# VCA.net
KiCad netlist of a schematic drawn in EAGLE
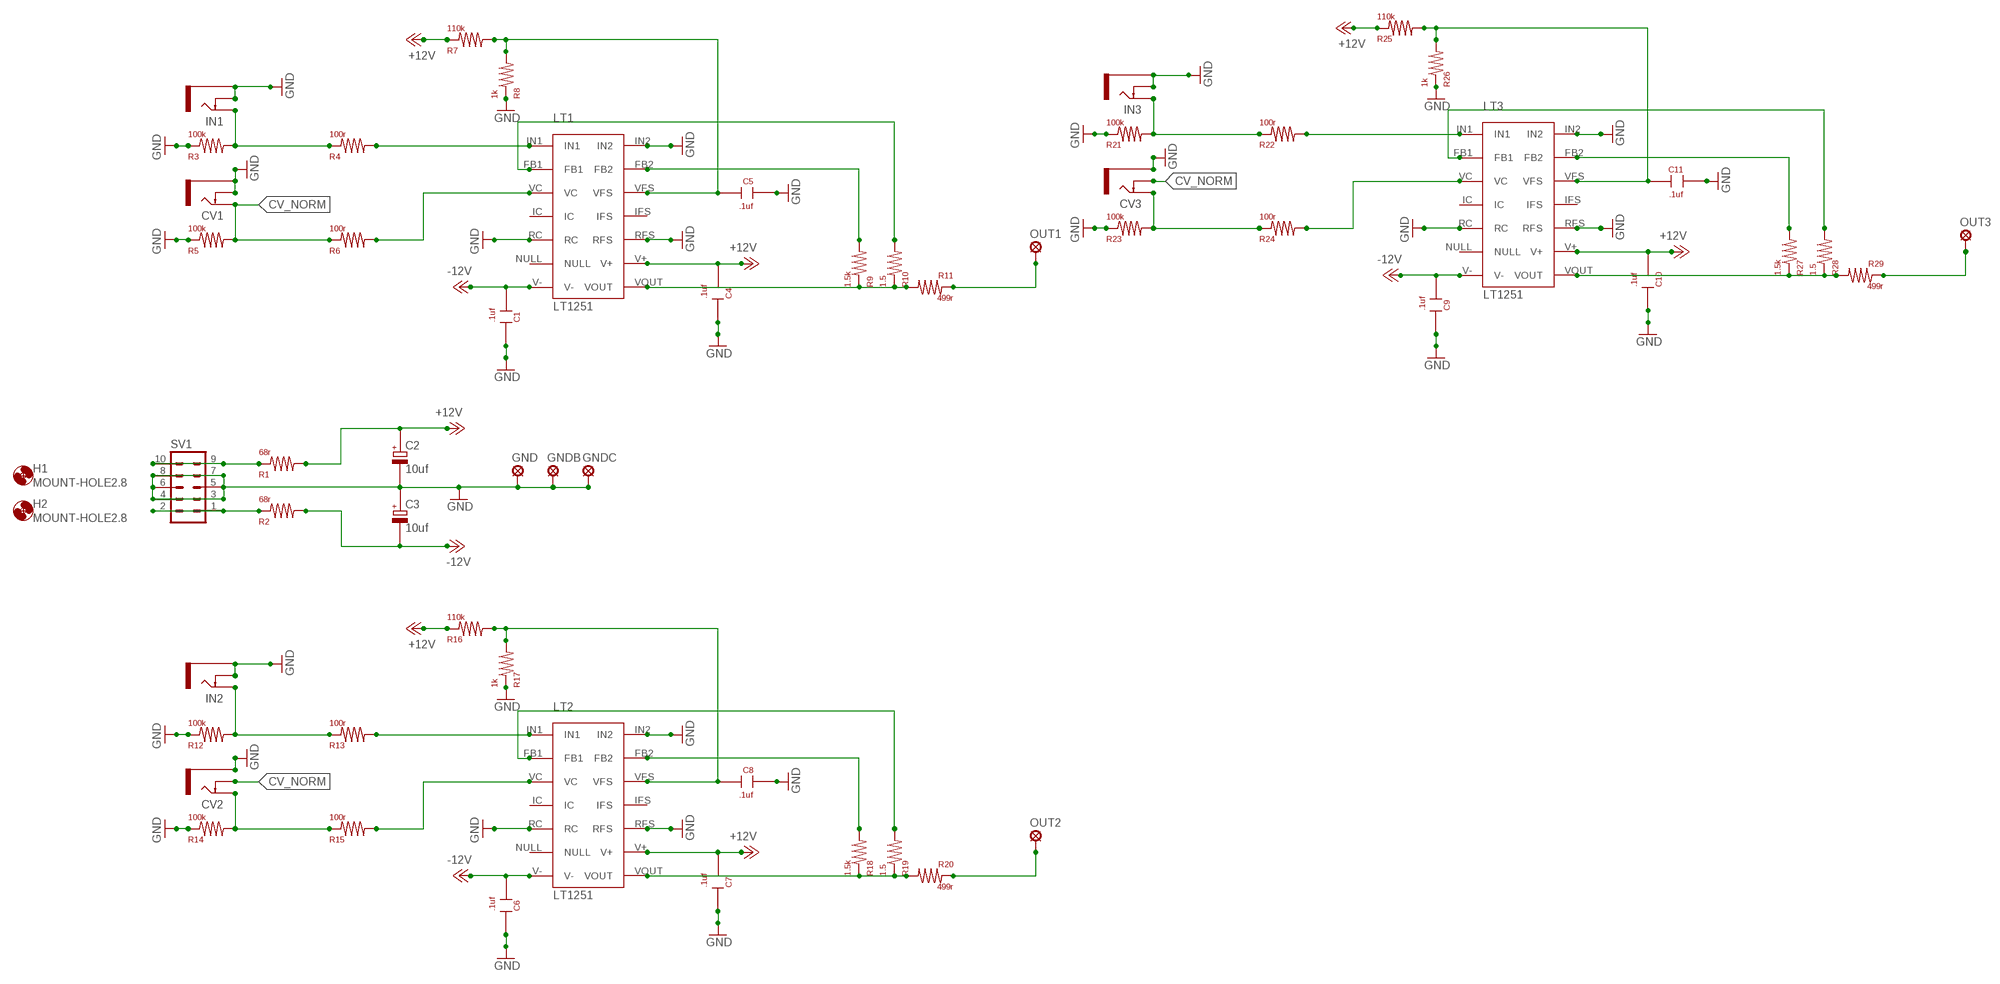
[diagram p0: schematic, sheet 1]

(export (version "E")
  (design (tool "Eeschema 10.0.6"))
  (components
    (comp (ref "C1")
      (value ".1uf")
      (footprint "eagle-import:CAPACITOR_FILM")
      (libsource (lib "eagle-import") (part "CAPACITOR_FILM"))
    )
    (comp (ref "C2")
      (value "10uf")
      (footprint "eagle-import:CAPACITOR_ELECTRO")
      (libsource (lib "eagle-import") (part "CAPACITOR_ELECTRO"))
    )
    (comp (ref "C3")
      (value "10uf")
      (footprint "eagle-import:CAPACITOR_ELECTRO")
      (libsource (lib "eagle-import") (part "CAPACITOR_ELECTRO"))
    )
    (comp (ref "C4")
      (value ".1uf")
      (footprint "eagle-import:CAPACITOR_FILM")
      (libsource (lib "eagle-import") (part "CAPACITOR_FILM"))
    )
    (comp (ref "C5")
      (value ".1uf")
      (footprint "eagle-import:CAPACITOR_FILM")
      (libsource (lib "eagle-import") (part "CAPACITOR_FILM"))
    )
    (comp (ref "C6")
      (value ".1uf")
      (footprint "eagle-import:CAPACITOR_FILM")
      (libsource (lib "eagle-import") (part "CAPACITOR_FILM"))
    )
    (comp (ref "C7")
      (value ".1uf")
      (footprint "eagle-import:CAPACITOR_FILM")
      (libsource (lib "eagle-import") (part "CAPACITOR_FILM"))
    )
    (comp (ref "C8")
      (value ".1uf")
      (footprint "eagle-import:CAPACITOR_FILM")
      (libsource (lib "eagle-import") (part "CAPACITOR_FILM"))
    )
    (comp (ref "C9")
      (value ".1uf")
      (footprint "eagle-import:CAPACITOR_FILM")
      (libsource (lib "eagle-import") (part "CAPACITOR_FILM"))
    )
    (comp (ref "C10")
      (value ".1uf")
      (footprint "eagle-import:CAPACITOR_FILM")
      (libsource (lib "eagle-import") (part "CAPACITOR_FILM"))
    )
    (comp (ref "C11")
      (value ".1uf")
      (footprint "eagle-import:CAPACITOR_FILM")
      (libsource (lib "eagle-import") (part "CAPACITOR_FILM"))
    )
    (comp (ref "CV1")
      (value "PJ302M")
      (footprint "eagle-import:PJ302M")
      (libsource (lib "eagle-import") (part "PJ302M"))
    )
    (comp (ref "CV2")
      (value "PJ302M")
      (footprint "eagle-import:PJ302M")
      (libsource (lib "eagle-import") (part "PJ302M"))
    )
    (comp (ref "CV3")
      (value "PJ302M")
      (footprint "eagle-import:PJ302M")
      (libsource (lib "eagle-import") (part "PJ302M"))
    )
    (comp (ref "GND")
      (value "LSP10")
      (footprint "eagle-import:LSP10")
      (libsource (lib "eagle-import") (part "LSP10"))
    )
    (comp (ref "GNDB")
      (value "LSP10")
      (footprint "eagle-import:LSP10")
      (libsource (lib "eagle-import") (part "LSP10"))
    )
    (comp (ref "GNDC")
      (value "LSP10")
      (footprint "eagle-import:LSP10")
      (libsource (lib "eagle-import") (part "LSP10"))
    )
    (comp (ref "H1")
      (value "MOUNT-HOLE2.8")
      (footprint "eagle-import:2,8")
      (libsource (lib "eagle-import") (part "MOUNT-HOLE2.8"))
    )
    (comp (ref "H2")
      (value "MOUNT-HOLE2.8")
      (footprint "eagle-import:2,8")
      (libsource (lib "eagle-import") (part "MOUNT-HOLE2.8"))
    )
    (comp (ref "IN1")
      (value "PJ302M")
      (footprint "eagle-import:PJ302M")
      (libsource (lib "eagle-import") (part "PJ302M"))
    )
    (comp (ref "IN2")
      (value "PJ302M")
      (footprint "eagle-import:PJ302M")
      (libsource (lib "eagle-import") (part "PJ302M"))
    )
    (comp (ref "IN3")
      (value "PJ302M")
      (footprint "eagle-import:PJ302M")
      (libsource (lib "eagle-import") (part "PJ302M"))
    )
    (comp (ref "LT1")
      (value "LT1251")
      (footprint "eagle-import:TL1251")
      (libsource (lib "eagle-import") (part "LT1251"))
    )
    (comp (ref "LT2")
      (value "LT1251")
      (footprint "eagle-import:TL1251")
      (libsource (lib "eagle-import") (part "LT1251"))
    )
    (comp (ref "LT3")
      (value "LT1251")
      (footprint "eagle-import:TL1251")
      (libsource (lib "eagle-import") (part "LT1251"))
    )
    (comp (ref "OUT1")
      (value "LSP10")
      (footprint "eagle-import:LSP10")
      (libsource (lib "eagle-import") (part "LSP10"))
    )
    (comp (ref "OUT2")
      (value "LSP10")
      (footprint "eagle-import:LSP10")
      (libsource (lib "eagle-import") (part "LSP10"))
    )
    (comp (ref "OUT3")
      (value "LSP10")
      (footprint "eagle-import:LSP10")
      (libsource (lib "eagle-import") (part "LSP10"))
    )
    (comp (ref "R1")
      (value "68r")
      (footprint "eagle-import:RESISTOR")
      (libsource (lib "eagle-import") (part "RESISTOR"))
    )
    (comp (ref "R2")
      (value "68r")
      (footprint "eagle-import:RESISTOR")
      (libsource (lib "eagle-import") (part "RESISTOR"))
    )
    (comp (ref "R3")
      (value "100k")
      (footprint "eagle-import:RESISTOR")
      (libsource (lib "eagle-import") (part "RESISTOR"))
    )
    (comp (ref "R4")
      (value "100r")
      (footprint "eagle-import:RESISTOR")
      (libsource (lib "eagle-import") (part "RESISTOR"))
    )
    (comp (ref "R5")
      (value "100k")
      (footprint "eagle-import:RESISTOR")
      (libsource (lib "eagle-import") (part "RESISTOR"))
    )
    (comp (ref "R6")
      (value "100r")
      (footprint "eagle-import:RESISTOR")
      (libsource (lib "eagle-import") (part "RESISTOR"))
    )
    (comp (ref "R7")
      (value "110k")
      (footprint "eagle-import:RESISTOR")
      (libsource (lib "eagle-import") (part "RESISTOR"))
    )
    (comp (ref "R8")
      (value "1k")
      (footprint "eagle-import:RESISTOR")
      (libsource (lib "eagle-import") (part "RESISTOR"))
    )
    (comp (ref "R9")
      (value "1.5k")
      (footprint "eagle-import:RESISTOR")
      (libsource (lib "eagle-import") (part "RESISTOR"))
    )
    (comp (ref "R10")
      (value "1.5")
      (footprint "eagle-import:RESISTOR")
      (libsource (lib "eagle-import") (part "RESISTOR"))
    )
    (comp (ref "R11")
      (value "499r")
      (footprint "eagle-import:RESISTOR")
      (libsource (lib "eagle-import") (part "RESISTOR"))
    )
    (comp (ref "R12")
      (value "100k")
      (footprint "eagle-import:RESISTOR")
      (libsource (lib "eagle-import") (part "RESISTOR"))
    )
    (comp (ref "R13")
      (value "100r")
      (footprint "eagle-import:RESISTOR")
      (libsource (lib "eagle-import") (part "RESISTOR"))
    )
    (comp (ref "R14")
      (value "100k")
      (footprint "eagle-import:RESISTOR")
      (libsource (lib "eagle-import") (part "RESISTOR"))
    )
    (comp (ref "R15")
      (value "100r")
      (footprint "eagle-import:RESISTOR")
      (libsource (lib "eagle-import") (part "RESISTOR"))
    )
    (comp (ref "R16")
      (value "110k")
      (footprint "eagle-import:RESISTOR")
      (libsource (lib "eagle-import") (part "RESISTOR"))
    )
    (comp (ref "R17")
      (value "1k")
      (footprint "eagle-import:RESISTOR")
      (libsource (lib "eagle-import") (part "RESISTOR"))
    )
    (comp (ref "R18")
      (value "1.5k")
      (footprint "eagle-import:RESISTOR")
      (libsource (lib "eagle-import") (part "RESISTOR"))
    )
    (comp (ref "R19")
      (value "1.5")
      (footprint "eagle-import:RESISTOR")
      (libsource (lib "eagle-import") (part "RESISTOR"))
    )
    (comp (ref "R20")
      (value "499r")
      (footprint "eagle-import:RESISTOR")
      (libsource (lib "eagle-import") (part "RESISTOR"))
    )
    (comp (ref "R21")
      (value "100k")
      (footprint "eagle-import:RESISTOR")
      (libsource (lib "eagle-import") (part "RESISTOR"))
    )
    (comp (ref "R22")
      (value "100r")
      (footprint "eagle-import:RESISTOR")
      (libsource (lib "eagle-import") (part "RESISTOR"))
    )
    (comp (ref "R23")
      (value "100k")
      (footprint "eagle-import:RESISTOR")
      (libsource (lib "eagle-import") (part "RESISTOR"))
    )
    (comp (ref "R24")
      (value "100r")
      (footprint "eagle-import:RESISTOR")
      (libsource (lib "eagle-import") (part "RESISTOR"))
    )
    (comp (ref "R25")
      (value "110k")
      (footprint "eagle-import:RESISTOR")
      (libsource (lib "eagle-import") (part "RESISTOR"))
    )
    (comp (ref "R26")
      (value "1k")
      (footprint "eagle-import:RESISTOR")
      (libsource (lib "eagle-import") (part "RESISTOR"))
    )
    (comp (ref "R27")
      (value "1.5k")
      (footprint "eagle-import:RESISTOR")
      (libsource (lib "eagle-import") (part "RESISTOR"))
    )
    (comp (ref "R28")
      (value "1.5")
      (footprint "eagle-import:RESISTOR")
      (libsource (lib "eagle-import") (part "RESISTOR"))
    )
    (comp (ref "R29")
      (value "499r")
      (footprint "eagle-import:RESISTOR")
      (libsource (lib "eagle-import") (part "RESISTOR"))
    )
    (comp (ref "SV1")
      (value "EURORACK10")
      (footprint "eagle-import:EURORACK10")
      (libsource (lib "eagle-import") (part "EURORACK10"))
    )
  )
  (nets
    (net (code "1") (name "+12V") (class "Default")
      (node (ref "C10") (pin "P$2") (pinfunction "P$2_P$2") (pintype "bidirectional"))
      (node (ref "C2") (pin "+") (pinfunction "P$2_+") (pintype "bidirectional"))
      (node (ref "C4") (pin "P$2") (pinfunction "P$2_P$2") (pintype "bidirectional"))
      (node (ref "C7") (pin "P$2") (pinfunction "P$2_P$2") (pintype "bidirectional"))
      (node (ref "LT1") (pin "V+") (pinfunction "V+_V+") (pintype "bidirectional"))
      (node (ref "LT2") (pin "V+") (pinfunction "V+_V+") (pintype "bidirectional"))
      (node (ref "LT3") (pin "V+") (pinfunction "V+_V+") (pintype "bidirectional"))
      (node (ref "R1") (pin "P$2") (pinfunction "P$2_P$2") (pintype "bidirectional"))
      (node (ref "R16") (pin "P$1") (pinfunction "P$1_P$1") (pintype "bidirectional"))
      (node (ref "R25") (pin "P$1") (pinfunction "P$1_P$1") (pintype "bidirectional"))
      (node (ref "R7") (pin "P$1") (pinfunction "P$1_P$1") (pintype "bidirectional"))
    )
    (net (code "2") (name "-12V") (class "Default")
      (node (ref "C1") (pin "P$2") (pinfunction "P$2_P$2") (pintype "bidirectional"))
      (node (ref "C3") (pin "-") (pinfunction "P$1_-") (pintype "bidirectional"))
      (node (ref "C6") (pin "P$2") (pinfunction "P$2_P$2") (pintype "bidirectional"))
      (node (ref "C9") (pin "P$2") (pinfunction "P$2_P$2") (pintype "bidirectional"))
      (node (ref "LT1") (pin "V-") (pinfunction "V-_V-") (pintype "bidirectional"))
      (node (ref "LT2") (pin "V-") (pinfunction "V-_V-") (pintype "bidirectional"))
      (node (ref "LT3") (pin "V-") (pinfunction "V-_V-") (pintype "bidirectional"))
      (node (ref "R2") (pin "P$2") (pinfunction "P$2_P$2") (pintype "bidirectional"))
    )
    (net (code "3") (name "CV_NORM") (class "Default")
      (node (ref "CV1") (pin "TIP") (pinfunction "TIP_TIP") (pintype "passive"))
      (node (ref "CV2") (pin "SW") (pinfunction "SWITCH_SW") (pintype "passive"))
      (node (ref "CV3") (pin "SW") (pinfunction "SWITCH_SW") (pintype "passive"))
      (node (ref "R5") (pin "P$2") (pinfunction "P$2_P$2") (pintype "bidirectional"))
      (node (ref "R6") (pin "P$1") (pinfunction "P$1_P$1") (pintype "bidirectional"))
    )
    (net (code "4") (name "GND") (class "Default")
      (node (ref "C1") (pin "P$1") (pinfunction "P$1_P$1") (pintype "bidirectional"))
      (node (ref "C10") (pin "P$1") (pinfunction "P$1_P$1") (pintype "bidirectional"))
      (node (ref "C11") (pin "P$1") (pinfunction "P$1_P$1") (pintype "bidirectional"))
      (node (ref "C2") (pin "-") (pinfunction "P$1_-") (pintype "bidirectional"))
      (node (ref "C3") (pin "+") (pinfunction "P$2_+") (pintype "bidirectional"))
      (node (ref "C4") (pin "P$1") (pinfunction "P$1_P$1") (pintype "bidirectional"))
      (node (ref "C5") (pin "P$1") (pinfunction "P$1_P$1") (pintype "bidirectional"))
      (node (ref "C6") (pin "P$1") (pinfunction "P$1_P$1") (pintype "bidirectional"))
      (node (ref "C7") (pin "P$1") (pinfunction "P$1_P$1") (pintype "bidirectional"))
      (node (ref "C8") (pin "P$1") (pinfunction "P$1_P$1") (pintype "bidirectional"))
      (node (ref "C9") (pin "P$1") (pinfunction "P$1_P$1") (pintype "bidirectional"))
      (node (ref "CV1") (pin "GND") (pinfunction "SLEEVE_GND") (pintype "passive"))
      (node (ref "CV1") (pin "SW") (pinfunction "SWITCH_SW") (pintype "passive"))
      (node (ref "CV2") (pin "GND") (pinfunction "SLEEVE_GND") (pintype "passive"))
      (node (ref "CV3") (pin "GND") (pinfunction "SLEEVE_GND") (pintype "passive"))
      (node (ref "GND") (pin "MP") (pinfunction "MP_MP") (pintype "passive"))
      (node (ref "GNDB") (pin "MP") (pinfunction "MP_MP") (pintype "passive"))
      (node (ref "GNDC") (pin "MP") (pinfunction "MP_MP") (pintype "passive"))
      (node (ref "IN1") (pin "GND") (pinfunction "SLEEVE_GND") (pintype "passive"))
      (node (ref "IN1") (pin "SW") (pinfunction "SWITCH_SW") (pintype "passive"))
      (node (ref "IN2") (pin "GND") (pinfunction "SLEEVE_GND") (pintype "passive"))
      (node (ref "IN2") (pin "SW") (pinfunction "SWITCH_SW") (pintype "passive"))
      (node (ref "IN3") (pin "GND") (pinfunction "SLEEVE_GND") (pintype "passive"))
      (node (ref "IN3") (pin "SW") (pinfunction "SWITCH_SW") (pintype "passive"))
      (node (ref "LT1") (pin "IN2") (pinfunction "IN2_IN2") (pintype "bidirectional"))
      (node (ref "LT1") (pin "RC") (pinfunction "RC_RC") (pintype "bidirectional"))
      (node (ref "LT1") (pin "RFS") (pinfunction "RFS_RFS") (pintype "bidirectional"))
      (node (ref "LT2") (pin "IN2") (pinfunction "IN2_IN2") (pintype "bidirectional"))
      (node (ref "LT2") (pin "RC") (pinfunction "RC_RC") (pintype "bidirectional"))
      (node (ref "LT2") (pin "RFS") (pinfunction "RFS_RFS") (pintype "bidirectional"))
      (node (ref "LT3") (pin "IN2") (pinfunction "IN2_IN2") (pintype "bidirectional"))
      (node (ref "LT3") (pin "RC") (pinfunction "RC_RC") (pintype "bidirectional"))
      (node (ref "LT3") (pin "RFS") (pinfunction "RFS_RFS") (pintype "bidirectional"))
      (node (ref "R12") (pin "P$1") (pinfunction "P$1_P$1") (pintype "bidirectional"))
      (node (ref "R14") (pin "P$1") (pinfunction "P$1_P$1") (pintype "bidirectional"))
      (node (ref "R17") (pin "P$1") (pinfunction "P$1_P$1") (pintype "bidirectional"))
      (node (ref "R21") (pin "P$1") (pinfunction "P$1_P$1") (pintype "bidirectional"))
      (node (ref "R23") (pin "P$1") (pinfunction "P$1_P$1") (pintype "bidirectional"))
      (node (ref "R26") (pin "P$1") (pinfunction "P$1_P$1") (pintype "bidirectional"))
      (node (ref "R3") (pin "P$1") (pinfunction "P$1_P$1") (pintype "bidirectional"))
      (node (ref "R5") (pin "P$1") (pinfunction "P$1_P$1") (pintype "bidirectional"))
      (node (ref "R8") (pin "P$1") (pinfunction "P$1_P$1") (pintype "bidirectional"))
      (node (ref "SV1") (pin "3") (pinfunction "3_3") (pintype "passive"))
      (node (ref "SV1") (pin "4") (pinfunction "4_4") (pintype "passive"))
      (node (ref "SV1") (pin "5") (pinfunction "5_5") (pintype "passive"))
      (node (ref "SV1") (pin "6") (pinfunction "6_6") (pintype "passive"))
      (node (ref "SV1") (pin "7") (pinfunction "7_7") (pintype "passive"))
      (node (ref "SV1") (pin "8") (pinfunction "8_8") (pintype "passive"))
    )
    (net (code "5") (name "Net-(C5-PadP$2)") (class "Default")
      (node (ref "C5") (pin "P$2") (pinfunction "P$2_P$2") (pintype "bidirectional"))
      (node (ref "LT1") (pin "VFS") (pinfunction "VFS_VFS") (pintype "bidirectional"))
      (node (ref "R7") (pin "P$2") (pinfunction "P$2_P$2") (pintype "bidirectional"))
      (node (ref "R8") (pin "P$2") (pinfunction "P$2_P$2") (pintype "bidirectional"))
    )
    (net (code "6") (name "Net-(C8-PadP$2)") (class "Default")
      (node (ref "C8") (pin "P$2") (pinfunction "P$2_P$2") (pintype "bidirectional"))
      (node (ref "LT2") (pin "VFS") (pinfunction "VFS_VFS") (pintype "bidirectional"))
      (node (ref "R16") (pin "P$2") (pinfunction "P$2_P$2") (pintype "bidirectional"))
      (node (ref "R17") (pin "P$2") (pinfunction "P$2_P$2") (pintype "bidirectional"))
    )
    (net (code "7") (name "Net-(C11-PadP$2)") (class "Default")
      (node (ref "C11") (pin "P$2") (pinfunction "P$2_P$2") (pintype "bidirectional"))
      (node (ref "LT3") (pin "VFS") (pinfunction "VFS_VFS") (pintype "bidirectional"))
      (node (ref "R25") (pin "P$2") (pinfunction "P$2_P$2") (pintype "bidirectional"))
      (node (ref "R26") (pin "P$2") (pinfunction "P$2_P$2") (pintype "bidirectional"))
    )
    (net (code "8") (name "Net-(CV2-PadTIP)") (class "Default")
      (node (ref "CV2") (pin "TIP") (pinfunction "TIP_TIP") (pintype "passive"))
      (node (ref "R14") (pin "P$2") (pinfunction "P$2_P$2") (pintype "bidirectional"))
      (node (ref "R15") (pin "P$1") (pinfunction "P$1_P$1") (pintype "bidirectional"))
    )
    (net (code "9") (name "Net-(CV3-PadTIP)") (class "Default")
      (node (ref "CV3") (pin "TIP") (pinfunction "TIP_TIP") (pintype "passive"))
      (node (ref "R23") (pin "P$2") (pinfunction "P$2_P$2") (pintype "bidirectional"))
      (node (ref "R24") (pin "P$1") (pinfunction "P$1_P$1") (pintype "bidirectional"))
    )
    (net (code "10") (name "Net-(IN1-PadTIP)") (class "Default")
      (node (ref "IN1") (pin "TIP") (pinfunction "TIP_TIP") (pintype "passive"))
      (node (ref "R3") (pin "P$2") (pinfunction "P$2_P$2") (pintype "bidirectional"))
      (node (ref "R4") (pin "P$1") (pinfunction "P$1_P$1") (pintype "bidirectional"))
    )
    (net (code "11") (name "Net-(IN2-PadTIP)") (class "Default")
      (node (ref "IN2") (pin "TIP") (pinfunction "TIP_TIP") (pintype "passive"))
      (node (ref "R12") (pin "P$2") (pinfunction "P$2_P$2") (pintype "bidirectional"))
      (node (ref "R13") (pin "P$1") (pinfunction "P$1_P$1") (pintype "bidirectional"))
    )
    (net (code "12") (name "Net-(IN3-PadTIP)") (class "Default")
      (node (ref "IN3") (pin "TIP") (pinfunction "TIP_TIP") (pintype "passive"))
      (node (ref "R21") (pin "P$2") (pinfunction "P$2_P$2") (pintype "bidirectional"))
      (node (ref "R22") (pin "P$1") (pinfunction "P$1_P$1") (pintype "bidirectional"))
    )
    (net (code "13") (name "Net-(LT1-PadFB1)") (class "Default")
      (node (ref "LT1") (pin "FB1") (pinfunction "FB1_FB1") (pintype "bidirectional"))
      (node (ref "R10") (pin "P$2") (pinfunction "P$2_P$2") (pintype "bidirectional"))
    )
    (net (code "14") (name "Net-(LT1-PadFB2)") (class "Default")
      (node (ref "LT1") (pin "FB2") (pinfunction "FB2_FB2") (pintype "bidirectional"))
      (node (ref "R9") (pin "P$2") (pinfunction "P$2_P$2") (pintype "bidirectional"))
    )
    (net (code "15") (name "Net-(LT1-PadIN1)") (class "Default")
      (node (ref "LT1") (pin "IN1") (pinfunction "IN1_IN1") (pintype "bidirectional"))
      (node (ref "R4") (pin "P$2") (pinfunction "P$2_P$2") (pintype "bidirectional"))
    )
    (net (code "16") (name "Net-(LT1-PadVC)") (class "Default")
      (node (ref "LT1") (pin "VC") (pinfunction "VC_VC") (pintype "bidirectional"))
      (node (ref "R6") (pin "P$2") (pinfunction "P$2_P$2") (pintype "bidirectional"))
    )
    (net (code "17") (name "Net-(LT1-PadVOUT)") (class "Default")
      (node (ref "LT1") (pin "VOUT") (pinfunction "VOUT_VOUT") (pintype "bidirectional"))
      (node (ref "R10") (pin "P$1") (pinfunction "P$1_P$1") (pintype "bidirectional"))
      (node (ref "R11") (pin "P$2") (pinfunction "P$2_P$2") (pintype "bidirectional"))
      (node (ref "R9") (pin "P$1") (pinfunction "P$1_P$1") (pintype "bidirectional"))
    )
    (net (code "18") (name "Net-(LT2-PadFB1)") (class "Default")
      (node (ref "LT2") (pin "FB1") (pinfunction "FB1_FB1") (pintype "bidirectional"))
      (node (ref "R19") (pin "P$2") (pinfunction "P$2_P$2") (pintype "bidirectional"))
    )
    (net (code "19") (name "Net-(LT2-PadFB2)") (class "Default")
      (node (ref "LT2") (pin "FB2") (pinfunction "FB2_FB2") (pintype "bidirectional"))
      (node (ref "R18") (pin "P$2") (pinfunction "P$2_P$2") (pintype "bidirectional"))
    )
    (net (code "20") (name "Net-(LT2-PadIN1)") (class "Default")
      (node (ref "LT2") (pin "IN1") (pinfunction "IN1_IN1") (pintype "bidirectional"))
      (node (ref "R13") (pin "P$2") (pinfunction "P$2_P$2") (pintype "bidirectional"))
    )
    (net (code "21") (name "Net-(LT2-PadVC)") (class "Default")
      (node (ref "LT2") (pin "VC") (pinfunction "VC_VC") (pintype "bidirectional"))
      (node (ref "R15") (pin "P$2") (pinfunction "P$2_P$2") (pintype "bidirectional"))
    )
    (net (code "22") (name "Net-(LT2-PadVOUT)") (class "Default")
      (node (ref "LT2") (pin "VOUT") (pinfunction "VOUT_VOUT") (pintype "bidirectional"))
      (node (ref "R18") (pin "P$1") (pinfunction "P$1_P$1") (pintype "bidirectional"))
      (node (ref "R19") (pin "P$1") (pinfunction "P$1_P$1") (pintype "bidirectional"))
      (node (ref "R20") (pin "P$2") (pinfunction "P$2_P$2") (pintype "bidirectional"))
    )
    (net (code "23") (name "Net-(LT3-PadFB1)") (class "Default")
      (node (ref "LT3") (pin "FB1") (pinfunction "FB1_FB1") (pintype "bidirectional"))
      (node (ref "R28") (pin "P$2") (pinfunction "P$2_P$2") (pintype "bidirectional"))
    )
    (net (code "24") (name "Net-(LT3-PadFB2)") (class "Default")
      (node (ref "LT3") (pin "FB2") (pinfunction "FB2_FB2") (pintype "bidirectional"))
      (node (ref "R27") (pin "P$2") (pinfunction "P$2_P$2") (pintype "bidirectional"))
    )
    (net (code "25") (name "Net-(LT3-PadIN1)") (class "Default")
      (node (ref "LT3") (pin "IN1") (pinfunction "IN1_IN1") (pintype "bidirectional"))
      (node (ref "R22") (pin "P$2") (pinfunction "P$2_P$2") (pintype "bidirectional"))
    )
    (net (code "26") (name "Net-(LT3-PadVC)") (class "Default")
      (node (ref "LT3") (pin "VC") (pinfunction "VC_VC") (pintype "bidirectional"))
      (node (ref "R24") (pin "P$2") (pinfunction "P$2_P$2") (pintype "bidirectional"))
    )
    (net (code "27") (name "Net-(LT3-PadVOUT)") (class "Default")
      (node (ref "LT3") (pin "VOUT") (pinfunction "VOUT_VOUT") (pintype "bidirectional"))
      (node (ref "R27") (pin "P$1") (pinfunction "P$1_P$1") (pintype "bidirectional"))
      (node (ref "R28") (pin "P$1") (pinfunction "P$1_P$1") (pintype "bidirectional"))
      (node (ref "R29") (pin "P$2") (pinfunction "P$2_P$2") (pintype "bidirectional"))
    )
    (net (code "28") (name "Net-(OUT1-PadMP)") (class "Default")
      (node (ref "OUT1") (pin "MP") (pinfunction "MP_MP") (pintype "passive"))
      (node (ref "R11") (pin "P$1") (pinfunction "P$1_P$1") (pintype "bidirectional"))
    )
    (net (code "29") (name "Net-(OUT2-PadMP)") (class "Default")
      (node (ref "OUT2") (pin "MP") (pinfunction "MP_MP") (pintype "passive"))
      (node (ref "R20") (pin "P$1") (pinfunction "P$1_P$1") (pintype "bidirectional"))
    )
    (net (code "30") (name "Net-(OUT3-PadMP)") (class "Default")
      (node (ref "OUT3") (pin "MP") (pinfunction "MP_MP") (pintype "passive"))
      (node (ref "R29") (pin "P$1") (pinfunction "P$1_P$1") (pintype "bidirectional"))
    )
    (net (code "31") (name "Net-(R1-PadP$1)") (class "Default")
      (node (ref "R1") (pin "P$1") (pinfunction "P$1_P$1") (pintype "bidirectional"))
      (node (ref "SV1") (pin "10") (pinfunction "10_10") (pintype "passive"))
      (node (ref "SV1") (pin "9") (pinfunction "9_9") (pintype "passive"))
    )
    (net (code "32") (name "Net-(R2-PadP$1)") (class "Default")
      (node (ref "R2") (pin "P$1") (pinfunction "P$1_P$1") (pintype "bidirectional"))
      (node (ref "SV1") (pin "1") (pinfunction "1_1") (pintype "passive"))
      (node (ref "SV1") (pin "2") (pinfunction "2_2") (pintype "passive"))
    )
    (net (code "33") (name "unconnected-(LT1-PadIC)") (class "Default")
      (node (ref "LT1") (pin "IC") (pinfunction "IC_IC") (pintype "bidirectional"))
    )
    (net (code "34") (name "unconnected-(LT1-PadIFS)") (class "Default")
      (node (ref "LT1") (pin "IFS") (pinfunction "IFS_IFS") (pintype "bidirectional"))
    )
    (net (code "35") (name "unconnected-(LT1-PadNULL)") (class "Default")
      (node (ref "LT1") (pin "NULL") (pinfunction "NULL_NULL") (pintype "bidirectional"))
    )
    (net (code "36") (name "unconnected-(LT2-PadIC)") (class "Default")
      (node (ref "LT2") (pin "IC") (pinfunction "IC_IC") (pintype "bidirectional"))
    )
    (net (code "37") (name "unconnected-(LT2-PadIFS)") (class "Default")
      (node (ref "LT2") (pin "IFS") (pinfunction "IFS_IFS") (pintype "bidirectional"))
    )
    (net (code "38") (name "unconnected-(LT2-PadNULL)") (class "Default")
      (node (ref "LT2") (pin "NULL") (pinfunction "NULL_NULL") (pintype "bidirectional"))
    )
    (net (code "39") (name "unconnected-(LT3-PadIC)") (class "Default")
      (node (ref "LT3") (pin "IC") (pinfunction "IC_IC") (pintype "bidirectional"))
    )
    (net (code "40") (name "unconnected-(LT3-PadIFS)") (class "Default")
      (node (ref "LT3") (pin "IFS") (pinfunction "IFS_IFS") (pintype "bidirectional"))
    )
    (net (code "41") (name "unconnected-(LT3-PadNULL)") (class "Default")
      (node (ref "LT3") (pin "NULL") (pinfunction "NULL_NULL") (pintype "bidirectional"))
    )
  )
)
